# pipower.net
KiCad netlist of a schematic drawn in EAGLE
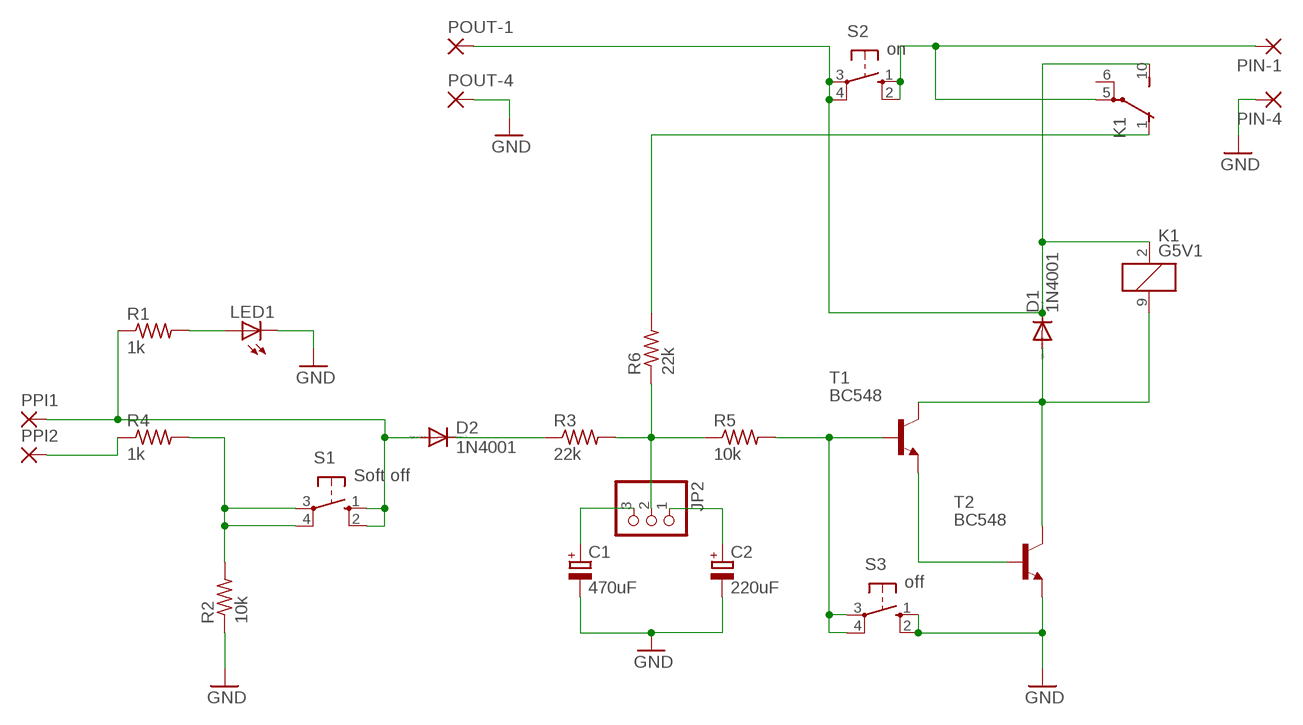
[diagram p0: schematic, sheet 1]

(export (version "E")
  (design (tool "Eeschema 10.0.6"))
  (components
    (comp (ref "C1")
      (value "470uF")
      (footprint "eagle-import:E2,5-7")
      (libsource (lib "eagle-import") (part "CPOL-EUE2.5-7"))
    )
    (comp (ref "C2")
      (value "220uF")
      (footprint "eagle-import:E2,5-6")
      (libsource (lib "eagle-import") (part "CPOL-EUE2.5-6"))
    )
    (comp (ref "D1")
      (value "1N4001")
      (footprint "eagle-import:DO41-10")
      (libsource (lib "eagle-import") (part "1N4004"))
    )
    (comp (ref "D2")
      (value "1N4001")
      (footprint "eagle-import:DO41-10")
      (libsource (lib "eagle-import") (part "1N4004"))
    )
    (comp (ref "JP2")
      (value "PINHD-1X3")
      (footprint "eagle-import:1X03")
      (libsource (lib "eagle-import") (part "PINHD-1X3"))
    )
    (comp (ref "K1")
      (value "G5V1")
      (footprint "eagle-import:G5V1")
      (fields (field (name "MPN") "G5V-1-DC24"))
      (libsource (lib "eagle-import") (part "G5V1"))
    )
    (comp (ref "LED1")
      (value "LED3MM")
      (footprint "eagle-import:LED3MM")
      (libsource (lib "eagle-import") (part "LED3MM"))
    )
    (comp (ref "PIN-1")
      (value "2,54/1,0")
      (footprint "eagle-import:2,54_1,0")
      (libsource (lib "eagle-import") (part "2,54/1,0"))
    )
    (comp (ref "PIN-4")
      (value "2,54/1,0")
      (footprint "eagle-import:2,54_1,0")
      (libsource (lib "eagle-import") (part "2,54/1,0"))
    )
    (comp (ref "POUT-1")
      (value "2,54/1,0")
      (footprint "eagle-import:2,54_1,0")
      (libsource (lib "eagle-import") (part "2,54/1,0"))
    )
    (comp (ref "POUT-4")
      (value "2,54/1,0")
      (footprint "eagle-import:2,54_1,0")
      (libsource (lib "eagle-import") (part "2,54/1,0"))
    )
    (comp (ref "PPI1")
      (value "2,54/1,0")
      (footprint "eagle-import:2,54_1,0")
      (libsource (lib "eagle-import") (part "2,54/1,0"))
    )
    (comp (ref "PPI2")
      (value "2,54/1,0")
      (footprint "eagle-import:2,54_1,0")
      (libsource (lib "eagle-import") (part "2,54/1,0"))
    )
    (comp (ref "R1")
      (value "1k")
      (footprint "eagle-import:0207_7")
      (libsource (lib "eagle-import") (part "R-US_0207/7"))
    )
    (comp (ref "R2")
      (value "10k")
      (footprint "eagle-import:0207_7")
      (libsource (lib "eagle-import") (part "R-US_0207/7"))
    )
    (comp (ref "R3")
      (value "22k")
      (footprint "eagle-import:0207_7")
      (libsource (lib "eagle-import") (part "R-US_0207/7"))
    )
    (comp (ref "R4")
      (value "1k")
      (footprint "eagle-import:0207_7")
      (libsource (lib "eagle-import") (part "R-US_0207/7"))
    )
    (comp (ref "R5")
      (value "10k")
      (footprint "eagle-import:0207_7")
      (libsource (lib "eagle-import") (part "R-US_0207/7"))
    )
    (comp (ref "R6")
      (value "22k")
      (footprint "eagle-import:0207_7")
      (libsource (lib "eagle-import") (part "R-US_0207/7"))
    )
    (comp (ref "S1")
      (value "Soft off")
      (footprint "eagle-import:B3F-10XX")
      (fields (field (name "MPN") "B3F-1000"))
      (libsource (lib "eagle-import") (part "10-XX"))
    )
    (comp (ref "S2")
      (value "on")
      (footprint "eagle-import:B3F-10XX")
      (fields (field (name "MPN") "B3F-1000"))
      (libsource (lib "eagle-import") (part "10-XX"))
    )
    (comp (ref "S3")
      (value "off")
      (footprint "eagle-import:B3F-10XX")
      (fields (field (name "MPN") "B3F-1000"))
      (libsource (lib "eagle-import") (part "10-XX"))
    )
    (comp (ref "T1")
      (value "BC548")
      (footprint "eagle-import:TO92-CBE")
      (libsource (lib "eagle-import") (part "-NPN-TO92-CBEBC548"))
    )
    (comp (ref "T2")
      (value "BC548")
      (footprint "eagle-import:TO92-CBE")
      (libsource (lib "eagle-import") (part "-NPN-TO92-CBEBC548"))
    )
  )
  (nets
    (net (code "1") (name "GND") (class "Default")
      (node (ref "C1") (pin "-") (pinfunction "-_-") (pintype "passive"))
      (node (ref "C2") (pin "-") (pinfunction "-_-") (pintype "passive"))
      (node (ref "LED1") (pin "K") (pinfunction "C_K") (pintype "passive"))
      (node (ref "PIN-4") (pin "1") (pinfunction "P_1") (pintype "passive"))
      (node (ref "POUT-4") (pin "1") (pinfunction "P_1") (pintype "passive"))
      (node (ref "R2") (pin "1") (pinfunction "1_1") (pintype "passive"))
      (node (ref "S3") (pin "1") (pinfunction "S_1") (pintype "passive"))
      (node (ref "S3") (pin "2") (pinfunction "S1_2") (pintype "passive"))
      (node (ref "T2") (pin "E") (pinfunction "E_E") (pintype "passive"))
    )
    (net (code "2") (name "Net-(C1-Pad+)") (class "Default")
      (node (ref "C1") (pin "+") (pinfunction "+_+") (pintype "passive"))
      (node (ref "JP2") (pin "3") (pinfunction "3_3") (pintype "passive"))
    )
    (net (code "3") (name "Net-(C2-Pad+)") (class "Default")
      (node (ref "C2") (pin "+") (pinfunction "+_+") (pintype "passive"))
      (node (ref "JP2") (pin "1") (pinfunction "1_1") (pintype "passive"))
    )
    (net (code "4") (name "Net-(D2-PadC)") (class "Default")
      (node (ref "D2") (pin "C") (pinfunction "C_C") (pintype "passive"))
      (node (ref "R3") (pin "1") (pinfunction "1_1") (pintype "passive"))
    )
    (net (code "5") (name "Net-(JP2-Pad2)") (class "Default")
      (node (ref "JP2") (pin "2") (pinfunction "2_2") (pintype "passive"))
      (node (ref "R3") (pin "2") (pinfunction "2_2") (pintype "passive"))
      (node (ref "R5") (pin "1") (pinfunction "1_1") (pintype "passive"))
      (node (ref "R6") (pin "1") (pinfunction "1_1") (pintype "passive"))
    )
    (net (code "6") (name "Net-(K1A-1)") (class "Default")
      (node (ref "D1") (pin "C") (pinfunction "C_C") (pintype "passive"))
      (node (ref "K1") (pin "10") (pinfunction "S_10") (pintype "passive"))
      (node (ref "K1") (pin "2") (pinfunction "1_2") (pintype "passive"))
      (node (ref "POUT-1") (pin "1") (pinfunction "P_1") (pintype "passive"))
      (node (ref "S2") (pin "3") (pinfunction "P_3") (pintype "passive"))
      (node (ref "S2") (pin "4") (pinfunction "P1_4") (pintype "passive"))
    )
    (net (code "7") (name "Net-(K1A-2)") (class "Default")
      (node (ref "D1") (pin "A") (pinfunction "A_A") (pintype "passive"))
      (node (ref "K1") (pin "9") (pinfunction "2_9") (pintype "passive"))
      (node (ref "T1") (pin "C") (pinfunction "C_C") (pintype "passive"))
      (node (ref "T2") (pin "C") (pinfunction "C_C") (pintype "passive"))
    )
    (net (code "8") (name "Net-(K1B-O)") (class "Default")
      (node (ref "K1") (pin "1") (pinfunction "O_1") (pintype "passive"))
      (node (ref "R6") (pin "2") (pinfunction "2_2") (pintype "passive"))
    )
    (net (code "9") (name "Net-(LED1-PadA)") (class "Default")
      (node (ref "LED1") (pin "A") (pinfunction "A_A") (pintype "passive"))
      (node (ref "R1") (pin "2") (pinfunction "2_2") (pintype "passive"))
    )
    (net (code "10") (name "Net-(PIN-1-P)") (class "Default")
      (node (ref "K1") (pin "5") (pinfunction "P_5") (pintype "passive"))
      (node (ref "PIN-1") (pin "1") (pinfunction "P_1") (pintype "passive"))
      (node (ref "S2") (pin "1") (pinfunction "S_1") (pintype "passive"))
      (node (ref "S2") (pin "2") (pinfunction "S1_2") (pintype "passive"))
    )
    (net (code "11") (name "Net-(PPI1-P)") (class "Default")
      (node (ref "D2") (pin "A") (pinfunction "A_A") (pintype "passive"))
      (node (ref "PPI1") (pin "1") (pinfunction "P_1") (pintype "passive"))
      (node (ref "R1") (pin "1") (pinfunction "1_1") (pintype "passive"))
      (node (ref "S1") (pin "1") (pinfunction "S_1") (pintype "passive"))
      (node (ref "S1") (pin "2") (pinfunction "S1_2") (pintype "passive"))
    )
    (net (code "12") (name "Net-(PPI2-P)") (class "Default")
      (node (ref "PPI2") (pin "1") (pinfunction "P_1") (pintype "passive"))
      (node (ref "R4") (pin "1") (pinfunction "1_1") (pintype "passive"))
    )
    (net (code "13") (name "Net-(S1-P)") (class "Default")
      (node (ref "R2") (pin "2") (pinfunction "2_2") (pintype "passive"))
      (node (ref "R4") (pin "2") (pinfunction "2_2") (pintype "passive"))
      (node (ref "S1") (pin "3") (pinfunction "P_3") (pintype "passive"))
      (node (ref "S1") (pin "4") (pinfunction "P1_4") (pintype "passive"))
    )
    (net (code "14") (name "Net-(S3-P)") (class "Default")
      (node (ref "R5") (pin "2") (pinfunction "2_2") (pintype "passive"))
      (node (ref "S3") (pin "3") (pinfunction "P_3") (pintype "passive"))
      (node (ref "S3") (pin "4") (pinfunction "P1_4") (pintype "passive"))
      (node (ref "T1") (pin "B") (pinfunction "B_B") (pintype "passive"))
    )
    (net (code "15") (name "Net-(T1-PadE)") (class "Default")
      (node (ref "T1") (pin "E") (pinfunction "E_E") (pintype "passive"))
      (node (ref "T2") (pin "B") (pinfunction "B_B") (pintype "passive"))
    )
    (net (code "16") (name "unconnected-(K1B-P-Pad6)") (class "Default")
      (node (ref "K1") (pin "6") (pinfunction "P_6") (pintype "passive"))
    )
  )
)
